# AIRZAI_LED_STRIP_FLEX_REVA_7p5Pitch.net
KiCad netlist of a schematic drawn in Altium Designer
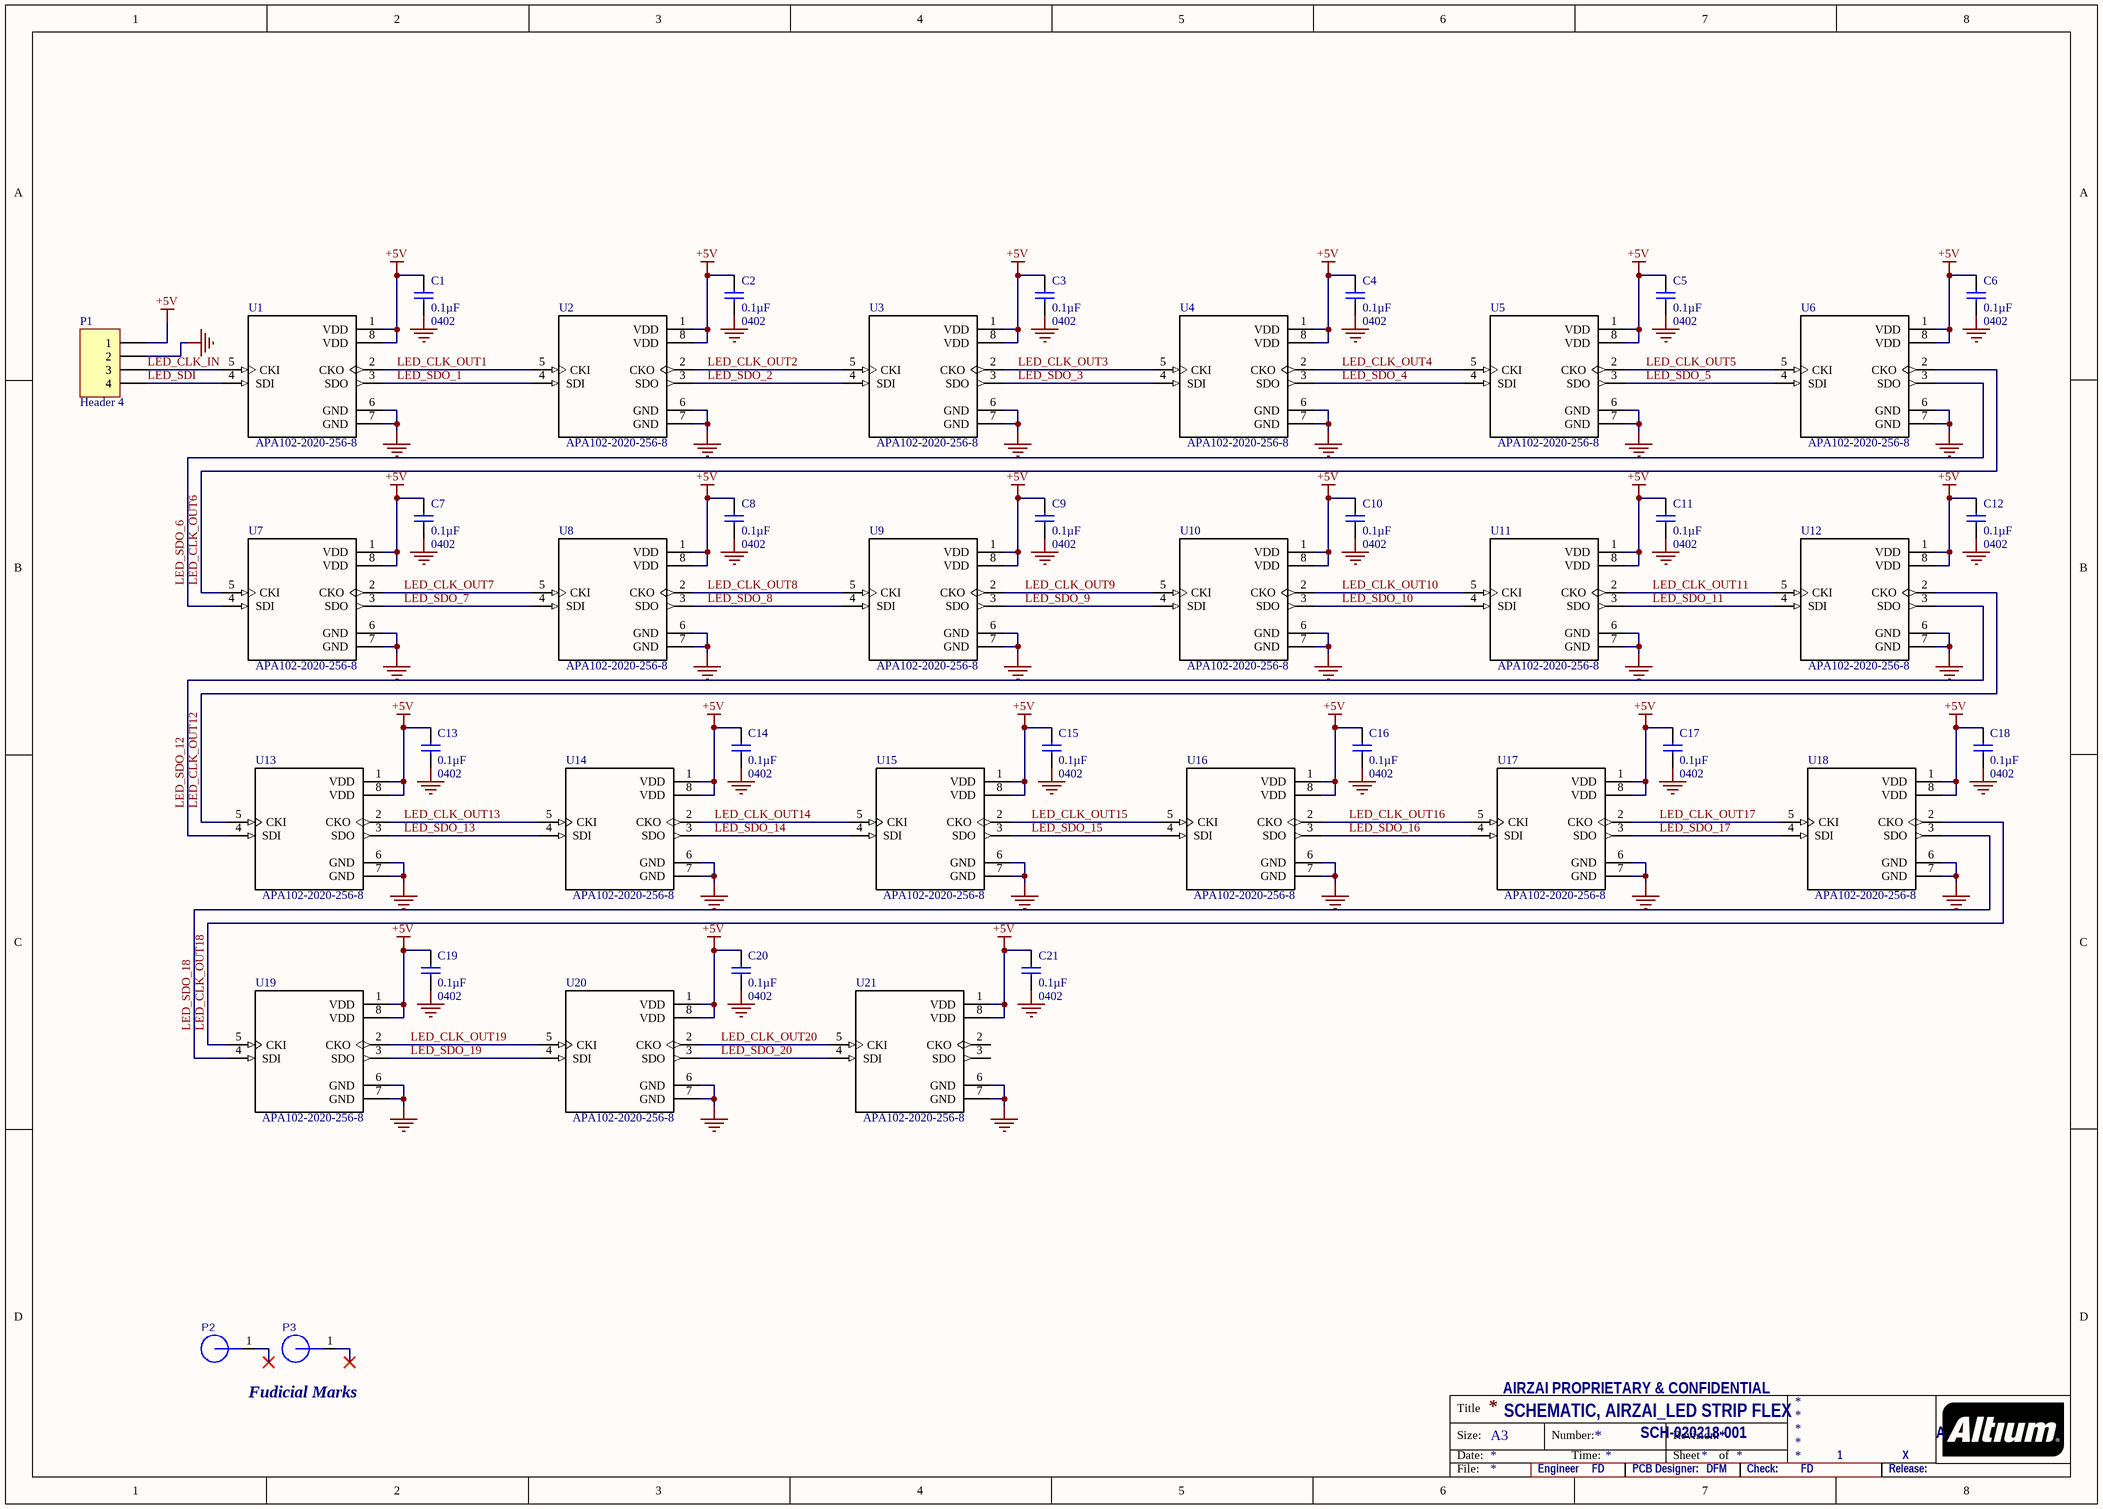
[diagram p0: AIRZAI_LED_STRIP_FLEX_REVA_7p5Pitch.SchDoc]

(export (version "E")
  (design (tool "Eeschema 10.0.6"))
  (components
    (comp (ref "C1")
      (value "0.1µF")
      (footprint "0402")
      (description "Capacitor, X7R, ±10%")
      (fields (field (name "MANUFACTURER") "TDK") (field (name "MANUFACTURER PART NUMBER") "C1005X7R1C104K"))
      (libsource (lib "Nordic Passive DB") (part "CAP"))
    )
    (comp (ref "C2")
      (value "0.1µF")
      (footprint "0402")
      (description "Capacitor, X7R, ±10%")
      (fields (field (name "MANUFACTURER") "TDK") (field (name "MANUFACTURER PART NUMBER") "C1005X7R1C104K"))
      (libsource (lib "Nordic Passive DB") (part "CAP"))
    )
    (comp (ref "C3")
      (value "0.1µF")
      (footprint "0402")
      (description "Capacitor, X7R, ±10%")
      (fields (field (name "MANUFACTURER") "TDK") (field (name "MANUFACTURER PART NUMBER") "C1005X7R1C104K"))
      (libsource (lib "Nordic Passive DB") (part "CAP"))
    )
    (comp (ref "C4")
      (value "0.1µF")
      (footprint "0402")
      (description "Capacitor, X7R, ±10%")
      (fields (field (name "MANUFACTURER") "TDK") (field (name "MANUFACTURER PART NUMBER") "C1005X7R1C104K"))
      (libsource (lib "Nordic Passive DB") (part "CAP"))
    )
    (comp (ref "C5")
      (value "0.1µF")
      (footprint "0402")
      (description "Capacitor, X7R, ±10%")
      (fields (field (name "MANUFACTURER") "TDK") (field (name "MANUFACTURER PART NUMBER") "C1005X7R1C104K"))
      (libsource (lib "Nordic Passive DB") (part "CAP"))
    )
    (comp (ref "C6")
      (value "0.1µF")
      (footprint "0402")
      (description "Capacitor, X7R, ±10%")
      (fields (field (name "MANUFACTURER") "TDK") (field (name "MANUFACTURER PART NUMBER") "C1005X7R1C104K"))
      (libsource (lib "Nordic Passive DB") (part "CAP"))
    )
    (comp (ref "C7")
      (value "0.1µF")
      (footprint "0402")
      (description "Capacitor, X7R, ±10%")
      (fields (field (name "MANUFACTURER") "TDK") (field (name "MANUFACTURER PART NUMBER") "C1005X7R1C104K"))
      (libsource (lib "Nordic Passive DB") (part "CAP"))
    )
    (comp (ref "C8")
      (value "0.1µF")
      (footprint "0402")
      (description "Capacitor, X7R, ±10%")
      (fields (field (name "MANUFACTURER") "TDK") (field (name "MANUFACTURER PART NUMBER") "C1005X7R1C104K"))
      (libsource (lib "Nordic Passive DB") (part "CAP"))
    )
    (comp (ref "C9")
      (value "0.1µF")
      (footprint "0402")
      (description "Capacitor, X7R, ±10%")
      (fields (field (name "MANUFACTURER") "TDK") (field (name "MANUFACTURER PART NUMBER") "C1005X7R1C104K"))
      (libsource (lib "Nordic Passive DB") (part "CAP"))
    )
    (comp (ref "C10")
      (value "0.1µF")
      (footprint "0402")
      (description "Capacitor, X7R, ±10%")
      (fields (field (name "MANUFACTURER") "TDK") (field (name "MANUFACTURER PART NUMBER") "C1005X7R1C104K"))
      (libsource (lib "Nordic Passive DB") (part "CAP"))
    )
    (comp (ref "C11")
      (value "0.1µF")
      (footprint "0402")
      (description "Capacitor, X7R, ±10%")
      (fields (field (name "MANUFACTURER") "TDK") (field (name "MANUFACTURER PART NUMBER") "C1005X7R1C104K"))
      (libsource (lib "Nordic Passive DB") (part "CAP"))
    )
    (comp (ref "C12")
      (value "0.1µF")
      (footprint "0402")
      (description "Capacitor, X7R, ±10%")
      (fields (field (name "MANUFACTURER") "TDK") (field (name "MANUFACTURER PART NUMBER") "C1005X7R1C104K"))
      (libsource (lib "Nordic Passive DB") (part "CAP"))
    )
    (comp (ref "C13")
      (value "0.1µF")
      (footprint "0402")
      (description "Capacitor, X7R, ±10%")
      (fields (field (name "MANUFACTURER") "TDK") (field (name "MANUFACTURER PART NUMBER") "C1005X7R1C104K"))
      (libsource (lib "Nordic Passive DB") (part "CAP"))
    )
    (comp (ref "C14")
      (value "0.1µF")
      (footprint "0402")
      (description "Capacitor, X7R, ±10%")
      (fields (field (name "MANUFACTURER") "TDK") (field (name "MANUFACTURER PART NUMBER") "C1005X7R1C104K"))
      (libsource (lib "Nordic Passive DB") (part "CAP"))
    )
    (comp (ref "C15")
      (value "0.1µF")
      (footprint "0402")
      (description "Capacitor, X7R, ±10%")
      (fields (field (name "MANUFACTURER") "TDK") (field (name "MANUFACTURER PART NUMBER") "C1005X7R1C104K"))
      (libsource (lib "Nordic Passive DB") (part "CAP"))
    )
    (comp (ref "C16")
      (value "0.1µF")
      (footprint "0402")
      (description "Capacitor, X7R, ±10%")
      (fields (field (name "MANUFACTURER") "TDK") (field (name "MANUFACTURER PART NUMBER") "C1005X7R1C104K"))
      (libsource (lib "Nordic Passive DB") (part "CAP"))
    )
    (comp (ref "C17")
      (value "0.1µF")
      (footprint "0402")
      (description "Capacitor, X7R, ±10%")
      (fields (field (name "MANUFACTURER") "TDK") (field (name "MANUFACTURER PART NUMBER") "C1005X7R1C104K"))
      (libsource (lib "Nordic Passive DB") (part "CAP"))
    )
    (comp (ref "C18")
      (value "0.1µF")
      (footprint "0402")
      (description "Capacitor, X7R, ±10%")
      (fields (field (name "MANUFACTURER") "TDK") (field (name "MANUFACTURER PART NUMBER") "C1005X7R1C104K"))
      (libsource (lib "Nordic Passive DB") (part "CAP"))
    )
    (comp (ref "C19")
      (value "0.1µF")
      (footprint "0402")
      (description "Capacitor, X7R, ±10%")
      (fields (field (name "MANUFACTURER") "TDK") (field (name "MANUFACTURER PART NUMBER") "C1005X7R1C104K"))
      (libsource (lib "Nordic Passive DB") (part "CAP"))
    )
    (comp (ref "C20")
      (value "0.1µF")
      (footprint "0402")
      (description "Capacitor, X7R, ±10%")
      (fields (field (name "MANUFACTURER") "TDK") (field (name "MANUFACTURER PART NUMBER") "C1005X7R1C104K"))
      (libsource (lib "Nordic Passive DB") (part "CAP"))
    )
    (comp (ref "C21")
      (value "0.1µF")
      (footprint "0402")
      (description "Capacitor, X7R, ±10%")
      (fields (field (name "MANUFACTURER") "TDK") (field (name "MANUFACTURER PART NUMBER") "C1005X7R1C104K"))
      (libsource (lib "Nordic Passive DB") (part "CAP"))
    )
    (comp (ref "P1")
      (value "Header 4")
      (footprint "FFC_4Pads")
      (description "Header, 4-Pin")
      (fields (field (name "PUBLISHER") "Altium Limited"))
      (libsource (lib "Miscellaneous Connectors") (part "Header 4"))
    )
    (comp (ref "P2") (value "~") (footprint "Fudicial") (libsource (lib "*") (part "TP")))
    (comp (ref "P3") (value "~") (footprint "Fudicial") (libsource (lib "*") (part "TP")))
    (comp (ref "U1")
      (value "APA102-2020-256-8")
      (footprint "APA102–2020")
      (description "DotStar Micro LEDs")
      (fields (field (name "MF") "Adafruit Industries") (field (name "MP") "APA-102-2020-256-8"))
      (libsource (lib "AIRZAI_LED_SENSE_FLEX_REVA") (part "APA102-2020-256-8"))
    )
    (comp (ref "U2")
      (value "APA102-2020-256-8")
      (footprint "APA102–2020")
      (description "DotStar Micro LEDs")
      (fields (field (name "MF") "Adafruit Industries") (field (name "MP") "APA-102-2020-256-8"))
      (libsource (lib "AIRZAI_LED_SENSE_FLEX_REVA") (part "APA102-2020-256-8"))
    )
    (comp (ref "U3")
      (value "APA102-2020-256-8")
      (footprint "APA102–2020")
      (description "DotStar Micro LEDs")
      (fields (field (name "MF") "Adafruit Industries") (field (name "MP") "APA-102-2020-256-8"))
      (libsource (lib "AIRZAI_LED_SENSE_FLEX_REVA") (part "APA102-2020-256-8"))
    )
    (comp (ref "U4")
      (value "APA102-2020-256-8")
      (footprint "APA102–2020")
      (description "DotStar Micro LEDs")
      (fields (field (name "MF") "Adafruit Industries") (field (name "MP") "APA-102-2020-256-8"))
      (libsource (lib "AIRZAI_LED_SENSE_FLEX_REVA") (part "APA102-2020-256-8"))
    )
    (comp (ref "U5")
      (value "APA102-2020-256-8")
      (footprint "APA102–2020")
      (description "DotStar Micro LEDs")
      (fields (field (name "MF") "Adafruit Industries") (field (name "MP") "APA-102-2020-256-8"))
      (libsource (lib "AIRZAI_LED_SENSE_FLEX_REVA") (part "APA102-2020-256-8"))
    )
    (comp (ref "U6")
      (value "APA102-2020-256-8")
      (footprint "APA102–2020")
      (description "DotStar Micro LEDs")
      (fields (field (name "MF") "Adafruit Industries") (field (name "MP") "APA-102-2020-256-8"))
      (libsource (lib "AIRZAI_LED_SENSE_FLEX_REVA") (part "APA102-2020-256-8"))
    )
    (comp (ref "U7")
      (value "APA102-2020-256-8")
      (footprint "APA102–2020")
      (description "DotStar Micro LEDs")
      (fields (field (name "MF") "Adafruit Industries") (field (name "MP") "APA-102-2020-256-8"))
      (libsource (lib "AIRZAI_LED_SENSE_FLEX_REVA") (part "APA102-2020-256-8"))
    )
    (comp (ref "U8")
      (value "APA102-2020-256-8")
      (footprint "APA102–2020")
      (description "DotStar Micro LEDs")
      (fields (field (name "MF") "Adafruit Industries") (field (name "MP") "APA-102-2020-256-8"))
      (libsource (lib "AIRZAI_LED_SENSE_FLEX_REVA") (part "APA102-2020-256-8"))
    )
    (comp (ref "U9")
      (value "APA102-2020-256-8")
      (footprint "APA102–2020")
      (description "DotStar Micro LEDs")
      (fields (field (name "MF") "Adafruit Industries") (field (name "MP") "APA-102-2020-256-8"))
      (libsource (lib "AIRZAI_LED_SENSE_FLEX_REVA") (part "APA102-2020-256-8"))
    )
    (comp (ref "U10")
      (value "APA102-2020-256-8")
      (footprint "APA102–2020")
      (description "DotStar Micro LEDs")
      (fields (field (name "MF") "Adafruit Industries") (field (name "MP") "APA-102-2020-256-8"))
      (libsource (lib "AIRZAI_LED_SENSE_FLEX_REVA") (part "APA102-2020-256-8"))
    )
    (comp (ref "U11")
      (value "APA102-2020-256-8")
      (footprint "APA102–2020")
      (description "DotStar Micro LEDs")
      (fields (field (name "MF") "Adafruit Industries") (field (name "MP") "APA-102-2020-256-8"))
      (libsource (lib "AIRZAI_LED_SENSE_FLEX_REVA") (part "APA102-2020-256-8"))
    )
    (comp (ref "U12")
      (value "APA102-2020-256-8")
      (footprint "APA102–2020")
      (description "DotStar Micro LEDs")
      (fields (field (name "MF") "Adafruit Industries") (field (name "MP") "APA-102-2020-256-8"))
      (libsource (lib "AIRZAI_LED_SENSE_FLEX_REVA") (part "APA102-2020-256-8"))
    )
    (comp (ref "U13")
      (value "APA102-2020-256-8")
      (footprint "APA102–2020")
      (description "DotStar Micro LEDs")
      (fields (field (name "MF") "Adafruit Industries") (field (name "MP") "APA-102-2020-256-8"))
      (libsource (lib "AIRZAI_LED_SENSE_FLEX_REVA") (part "APA102-2020-256-8"))
    )
    (comp (ref "U14")
      (value "APA102-2020-256-8")
      (footprint "APA102–2020")
      (description "DotStar Micro LEDs")
      (fields (field (name "MF") "Adafruit Industries") (field (name "MP") "APA-102-2020-256-8"))
      (libsource (lib "AIRZAI_LED_SENSE_FLEX_REVA") (part "APA102-2020-256-8"))
    )
    (comp (ref "U15")
      (value "APA102-2020-256-8")
      (footprint "APA102–2020")
      (description "DotStar Micro LEDs")
      (fields (field (name "MF") "Adafruit Industries") (field (name "MP") "APA-102-2020-256-8"))
      (libsource (lib "AIRZAI_LED_SENSE_FLEX_REVA") (part "APA102-2020-256-8"))
    )
    (comp (ref "U16")
      (value "APA102-2020-256-8")
      (footprint "APA102–2020")
      (description "DotStar Micro LEDs")
      (fields (field (name "MF") "Adafruit Industries") (field (name "MP") "APA-102-2020-256-8"))
      (libsource (lib "AIRZAI_LED_SENSE_FLEX_REVA") (part "APA102-2020-256-8"))
    )
    (comp (ref "U17")
      (value "APA102-2020-256-8")
      (footprint "APA102–2020")
      (description "DotStar Micro LEDs")
      (fields (field (name "MF") "Adafruit Industries") (field (name "MP") "APA-102-2020-256-8"))
      (libsource (lib "AIRZAI_LED_SENSE_FLEX_REVA") (part "APA102-2020-256-8"))
    )
    (comp (ref "U18")
      (value "APA102-2020-256-8")
      (footprint "APA102–2020")
      (description "DotStar Micro LEDs")
      (fields (field (name "MF") "Adafruit Industries") (field (name "MP") "APA-102-2020-256-8"))
      (libsource (lib "AIRZAI_LED_SENSE_FLEX_REVA") (part "APA102-2020-256-8"))
    )
    (comp (ref "U19")
      (value "APA102-2020-256-8")
      (footprint "APA102–2020")
      (description "DotStar Micro LEDs")
      (fields (field (name "MF") "Adafruit Industries") (field (name "MP") "APA-102-2020-256-8"))
      (libsource (lib "AIRZAI_LED_SENSE_FLEX_REVA") (part "APA102-2020-256-8"))
    )
    (comp (ref "U20")
      (value "APA102-2020-256-8")
      (footprint "APA102–2020")
      (description "DotStar Micro LEDs")
      (fields (field (name "MF") "Adafruit Industries") (field (name "MP") "APA-102-2020-256-8"))
      (libsource (lib "AIRZAI_LED_SENSE_FLEX_REVA") (part "APA102-2020-256-8"))
    )
    (comp (ref "U21")
      (value "APA102-2020-256-8")
      (footprint "APA102–2020")
      (description "DotStar Micro LEDs")
      (fields (field (name "MF") "Adafruit Industries") (field (name "MP") "APA-102-2020-256-8"))
      (libsource (lib "AIRZAI_LED_SENSE_FLEX_REVA") (part "APA102-2020-256-8"))
    )
  )
  (nets
    (net (code "1") (name "+5V") (class "Default")
      (node (ref "C1") (pin "1") (pinfunction "1_1") (pintype "passive"))
      (node (ref "C10") (pin "1") (pinfunction "1_1") (pintype "passive"))
      (node (ref "C11") (pin "1") (pinfunction "1_1") (pintype "passive"))
      (node (ref "C12") (pin "1") (pinfunction "1_1") (pintype "passive"))
      (node (ref "C13") (pin "1") (pinfunction "1_1") (pintype "passive"))
      (node (ref "C14") (pin "1") (pinfunction "1_1") (pintype "passive"))
      (node (ref "C15") (pin "1") (pinfunction "1_1") (pintype "passive"))
      (node (ref "C16") (pin "1") (pinfunction "1_1") (pintype "passive"))
      (node (ref "C17") (pin "1") (pinfunction "1_1") (pintype "passive"))
      (node (ref "C18") (pin "1") (pinfunction "1_1") (pintype "passive"))
      (node (ref "C19") (pin "1") (pinfunction "1_1") (pintype "passive"))
      (node (ref "C2") (pin "1") (pinfunction "1_1") (pintype "passive"))
      (node (ref "C20") (pin "1") (pinfunction "1_1") (pintype "passive"))
      (node (ref "C21") (pin "1") (pinfunction "1_1") (pintype "passive"))
      (node (ref "C3") (pin "1") (pinfunction "1_1") (pintype "passive"))
      (node (ref "C4") (pin "1") (pinfunction "1_1") (pintype "passive"))
      (node (ref "C5") (pin "1") (pinfunction "1_1") (pintype "passive"))
      (node (ref "C6") (pin "1") (pinfunction "1_1") (pintype "passive"))
      (node (ref "C7") (pin "1") (pinfunction "1_1") (pintype "passive"))
      (node (ref "C8") (pin "1") (pinfunction "1_1") (pintype "passive"))
      (node (ref "C9") (pin "1") (pinfunction "1_1") (pintype "passive"))
      (node (ref "P1") (pin "1") (pinfunction "1_1") (pintype "passive"))
      (node (ref "U1") (pin "1") (pinfunction "VDD_1") (pintype "power_in"))
      (node (ref "U1") (pin "8") (pinfunction "VDD_8") (pintype "power_in"))
      (node (ref "U10") (pin "1") (pinfunction "VDD_1") (pintype "power_in"))
      (node (ref "U10") (pin "8") (pinfunction "VDD_8") (pintype "power_in"))
      (node (ref "U11") (pin "1") (pinfunction "VDD_1") (pintype "power_in"))
      (node (ref "U11") (pin "8") (pinfunction "VDD_8") (pintype "power_in"))
      (node (ref "U12") (pin "1") (pinfunction "VDD_1") (pintype "power_in"))
      (node (ref "U12") (pin "8") (pinfunction "VDD_8") (pintype "power_in"))
      (node (ref "U13") (pin "1") (pinfunction "VDD_1") (pintype "power_in"))
      (node (ref "U13") (pin "8") (pinfunction "VDD_8") (pintype "power_in"))
      (node (ref "U14") (pin "1") (pinfunction "VDD_1") (pintype "power_in"))
      (node (ref "U14") (pin "8") (pinfunction "VDD_8") (pintype "power_in"))
      (node (ref "U15") (pin "1") (pinfunction "VDD_1") (pintype "power_in"))
      (node (ref "U15") (pin "8") (pinfunction "VDD_8") (pintype "power_in"))
      (node (ref "U16") (pin "1") (pinfunction "VDD_1") (pintype "power_in"))
      (node (ref "U16") (pin "8") (pinfunction "VDD_8") (pintype "power_in"))
      (node (ref "U17") (pin "1") (pinfunction "VDD_1") (pintype "power_in"))
      (node (ref "U17") (pin "8") (pinfunction "VDD_8") (pintype "power_in"))
      (node (ref "U18") (pin "1") (pinfunction "VDD_1") (pintype "power_in"))
      (node (ref "U18") (pin "8") (pinfunction "VDD_8") (pintype "power_in"))
      (node (ref "U19") (pin "1") (pinfunction "VDD_1") (pintype "power_in"))
      (node (ref "U19") (pin "8") (pinfunction "VDD_8") (pintype "power_in"))
      (node (ref "U2") (pin "1") (pinfunction "VDD_1") (pintype "power_in"))
      (node (ref "U2") (pin "8") (pinfunction "VDD_8") (pintype "power_in"))
      (node (ref "U20") (pin "1") (pinfunction "VDD_1") (pintype "power_in"))
      (node (ref "U20") (pin "8") (pinfunction "VDD_8") (pintype "power_in"))
      (node (ref "U21") (pin "1") (pinfunction "VDD_1") (pintype "power_in"))
      (node (ref "U21") (pin "8") (pinfunction "VDD_8") (pintype "power_in"))
      (node (ref "U3") (pin "1") (pinfunction "VDD_1") (pintype "power_in"))
      (node (ref "U3") (pin "8") (pinfunction "VDD_8") (pintype "power_in"))
      (node (ref "U4") (pin "1") (pinfunction "VDD_1") (pintype "power_in"))
      (node (ref "U4") (pin "8") (pinfunction "VDD_8") (pintype "power_in"))
      (node (ref "U5") (pin "1") (pinfunction "VDD_1") (pintype "power_in"))
      (node (ref "U5") (pin "8") (pinfunction "VDD_8") (pintype "power_in"))
      (node (ref "U6") (pin "1") (pinfunction "VDD_1") (pintype "power_in"))
      (node (ref "U6") (pin "8") (pinfunction "VDD_8") (pintype "power_in"))
      (node (ref "U7") (pin "1") (pinfunction "VDD_1") (pintype "power_in"))
      (node (ref "U7") (pin "8") (pinfunction "VDD_8") (pintype "power_in"))
      (node (ref "U8") (pin "1") (pinfunction "VDD_1") (pintype "power_in"))
      (node (ref "U8") (pin "8") (pinfunction "VDD_8") (pintype "power_in"))
      (node (ref "U9") (pin "1") (pinfunction "VDD_1") (pintype "power_in"))
      (node (ref "U9") (pin "8") (pinfunction "VDD_8") (pintype "power_in"))
    )
    (net (code "2") (name "/LED_CLK_IN") (class "Default")
      (node (ref "P1") (pin "3") (pinfunction "3_3") (pintype "passive"))
      (node (ref "U1") (pin "5") (pinfunction "CKI_5") (pintype "input"))
    )
    (net (code "3") (name "/LED_CLK_OUT1") (class "Default")
      (node (ref "U1") (pin "2") (pinfunction "CKO_2") (pintype "output"))
      (node (ref "U2") (pin "5") (pinfunction "CKI_5") (pintype "input"))
    )
    (net (code "4") (name "/LED_CLK_OUT2") (class "Default")
      (node (ref "U2") (pin "2") (pinfunction "CKO_2") (pintype "output"))
      (node (ref "U3") (pin "5") (pinfunction "CKI_5") (pintype "input"))
    )
    (net (code "5") (name "/LED_CLK_OUT3") (class "Default")
      (node (ref "U3") (pin "2") (pinfunction "CKO_2") (pintype "output"))
      (node (ref "U4") (pin "5") (pinfunction "CKI_5") (pintype "input"))
    )
    (net (code "6") (name "/LED_CLK_OUT4") (class "Default")
      (node (ref "U4") (pin "2") (pinfunction "CKO_2") (pintype "output"))
      (node (ref "U5") (pin "5") (pinfunction "CKI_5") (pintype "input"))
    )
    (net (code "7") (name "/LED_CLK_OUT5") (class "Default")
      (node (ref "U5") (pin "2") (pinfunction "CKO_2") (pintype "output"))
      (node (ref "U6") (pin "5") (pinfunction "CKI_5") (pintype "input"))
    )
    (net (code "8") (name "/LED_CLK_OUT6") (class "Default")
      (node (ref "U6") (pin "2") (pinfunction "CKO_2") (pintype "output"))
      (node (ref "U7") (pin "5") (pinfunction "CKI_5") (pintype "input"))
    )
    (net (code "9") (name "/LED_CLK_OUT7") (class "Default")
      (node (ref "U7") (pin "2") (pinfunction "CKO_2") (pintype "output"))
      (node (ref "U8") (pin "5") (pinfunction "CKI_5") (pintype "input"))
    )
    (net (code "10") (name "/LED_CLK_OUT8") (class "Default")
      (node (ref "U8") (pin "2") (pinfunction "CKO_2") (pintype "output"))
      (node (ref "U9") (pin "5") (pinfunction "CKI_5") (pintype "input"))
    )
    (net (code "11") (name "/LED_CLK_OUT9") (class "Default")
      (node (ref "U10") (pin "5") (pinfunction "CKI_5") (pintype "input"))
      (node (ref "U9") (pin "2") (pinfunction "CKO_2") (pintype "output"))
    )
    (net (code "12") (name "/LED_CLK_OUT10") (class "Default")
      (node (ref "U10") (pin "2") (pinfunction "CKO_2") (pintype "output"))
      (node (ref "U11") (pin "5") (pinfunction "CKI_5") (pintype "input"))
    )
    (net (code "13") (name "/LED_CLK_OUT11") (class "Default")
      (node (ref "U11") (pin "2") (pinfunction "CKO_2") (pintype "output"))
      (node (ref "U12") (pin "5") (pinfunction "CKI_5") (pintype "input"))
    )
    (net (code "14") (name "/LED_CLK_OUT12") (class "Default")
      (node (ref "U12") (pin "2") (pinfunction "CKO_2") (pintype "output"))
      (node (ref "U13") (pin "5") (pinfunction "CKI_5") (pintype "input"))
    )
    (net (code "15") (name "/LED_CLK_OUT13") (class "Default")
      (node (ref "U13") (pin "2") (pinfunction "CKO_2") (pintype "output"))
      (node (ref "U14") (pin "5") (pinfunction "CKI_5") (pintype "input"))
    )
    (net (code "16") (name "/LED_CLK_OUT14") (class "Default")
      (node (ref "U14") (pin "2") (pinfunction "CKO_2") (pintype "output"))
      (node (ref "U15") (pin "5") (pinfunction "CKI_5") (pintype "input"))
    )
    (net (code "17") (name "/LED_CLK_OUT15") (class "Default")
      (node (ref "U15") (pin "2") (pinfunction "CKO_2") (pintype "output"))
      (node (ref "U16") (pin "5") (pinfunction "CKI_5") (pintype "input"))
    )
    (net (code "18") (name "/LED_CLK_OUT16") (class "Default")
      (node (ref "U16") (pin "2") (pinfunction "CKO_2") (pintype "output"))
      (node (ref "U17") (pin "5") (pinfunction "CKI_5") (pintype "input"))
    )
    (net (code "19") (name "/LED_CLK_OUT17") (class "Default")
      (node (ref "U17") (pin "2") (pinfunction "CKO_2") (pintype "output"))
      (node (ref "U18") (pin "5") (pinfunction "CKI_5") (pintype "input"))
    )
    (net (code "20") (name "/LED_CLK_OUT18") (class "Default")
      (node (ref "U18") (pin "2") (pinfunction "CKO_2") (pintype "output"))
      (node (ref "U19") (pin "5") (pinfunction "CKI_5") (pintype "input"))
    )
    (net (code "21") (name "/LED_CLK_OUT19") (class "Default")
      (node (ref "U19") (pin "2") (pinfunction "CKO_2") (pintype "output"))
      (node (ref "U20") (pin "5") (pinfunction "CKI_5") (pintype "input"))
    )
    (net (code "22") (name "/LED_CLK_OUT20") (class "Default")
      (node (ref "U20") (pin "2") (pinfunction "CKO_2") (pintype "output"))
      (node (ref "U21") (pin "5") (pinfunction "CKI_5") (pintype "input"))
    )
    (net (code "23") (name "/LED_SDI") (class "Default")
      (node (ref "P1") (pin "4") (pinfunction "4_4") (pintype "passive"))
      (node (ref "U1") (pin "4") (pinfunction "SDI_4") (pintype "input"))
    )
    (net (code "24") (name "/LED_SDO_1") (class "Default")
      (node (ref "U1") (pin "3") (pinfunction "SDO_3") (pintype "output"))
      (node (ref "U2") (pin "4") (pinfunction "SDI_4") (pintype "input"))
    )
    (net (code "25") (name "/LED_SDO_2") (class "Default")
      (node (ref "U2") (pin "3") (pinfunction "SDO_3") (pintype "output"))
      (node (ref "U3") (pin "4") (pinfunction "SDI_4") (pintype "input"))
    )
    (net (code "26") (name "/LED_SDO_3") (class "Default")
      (node (ref "U3") (pin "3") (pinfunction "SDO_3") (pintype "output"))
      (node (ref "U4") (pin "4") (pinfunction "SDI_4") (pintype "input"))
    )
    (net (code "27") (name "/LED_SDO_4") (class "Default")
      (node (ref "U4") (pin "3") (pinfunction "SDO_3") (pintype "output"))
      (node (ref "U5") (pin "4") (pinfunction "SDI_4") (pintype "input"))
    )
    (net (code "28") (name "/LED_SDO_5") (class "Default")
      (node (ref "U5") (pin "3") (pinfunction "SDO_3") (pintype "output"))
      (node (ref "U6") (pin "4") (pinfunction "SDI_4") (pintype "input"))
    )
    (net (code "29") (name "/LED_SDO_6") (class "Default")
      (node (ref "U6") (pin "3") (pinfunction "SDO_3") (pintype "output"))
      (node (ref "U7") (pin "4") (pinfunction "SDI_4") (pintype "input"))
    )
    (net (code "30") (name "/LED_SDO_7") (class "Default")
      (node (ref "U7") (pin "3") (pinfunction "SDO_3") (pintype "output"))
      (node (ref "U8") (pin "4") (pinfunction "SDI_4") (pintype "input"))
    )
    (net (code "31") (name "/LED_SDO_8") (class "Default")
      (node (ref "U8") (pin "3") (pinfunction "SDO_3") (pintype "output"))
      (node (ref "U9") (pin "4") (pinfunction "SDI_4") (pintype "input"))
    )
    (net (code "32") (name "/LED_SDO_9") (class "Default")
      (node (ref "U10") (pin "4") (pinfunction "SDI_4") (pintype "input"))
      (node (ref "U9") (pin "3") (pinfunction "SDO_3") (pintype "output"))
    )
    (net (code "33") (name "/LED_SDO_10") (class "Default")
      (node (ref "U10") (pin "3") (pinfunction "SDO_3") (pintype "output"))
      (node (ref "U11") (pin "4") (pinfunction "SDI_4") (pintype "input"))
    )
    (net (code "34") (name "/LED_SDO_11") (class "Default")
      (node (ref "U11") (pin "3") (pinfunction "SDO_3") (pintype "output"))
      (node (ref "U12") (pin "4") (pinfunction "SDI_4") (pintype "input"))
    )
    (net (code "35") (name "/LED_SDO_12") (class "Default")
      (node (ref "U12") (pin "3") (pinfunction "SDO_3") (pintype "output"))
      (node (ref "U13") (pin "4") (pinfunction "SDI_4") (pintype "input"))
    )
    (net (code "36") (name "/LED_SDO_13") (class "Default")
      (node (ref "U13") (pin "3") (pinfunction "SDO_3") (pintype "output"))
      (node (ref "U14") (pin "4") (pinfunction "SDI_4") (pintype "input"))
    )
    (net (code "37") (name "/LED_SDO_14") (class "Default")
      (node (ref "U14") (pin "3") (pinfunction "SDO_3") (pintype "output"))
      (node (ref "U15") (pin "4") (pinfunction "SDI_4") (pintype "input"))
    )
    (net (code "38") (name "/LED_SDO_15") (class "Default")
      (node (ref "U15") (pin "3") (pinfunction "SDO_3") (pintype "output"))
      (node (ref "U16") (pin "4") (pinfunction "SDI_4") (pintype "input"))
    )
    (net (code "39") (name "/LED_SDO_16") (class "Default")
      (node (ref "U16") (pin "3") (pinfunction "SDO_3") (pintype "output"))
      (node (ref "U17") (pin "4") (pinfunction "SDI_4") (pintype "input"))
    )
    (net (code "40") (name "/LED_SDO_17") (class "Default")
      (node (ref "U17") (pin "3") (pinfunction "SDO_3") (pintype "output"))
      (node (ref "U18") (pin "4") (pinfunction "SDI_4") (pintype "input"))
    )
    (net (code "41") (name "/LED_SDO_18") (class "Default")
      (node (ref "U18") (pin "3") (pinfunction "SDO_3") (pintype "output"))
      (node (ref "U19") (pin "4") (pinfunction "SDI_4") (pintype "input"))
    )
    (net (code "42") (name "/LED_SDO_19") (class "Default")
      (node (ref "U19") (pin "3") (pinfunction "SDO_3") (pintype "output"))
      (node (ref "U20") (pin "4") (pinfunction "SDI_4") (pintype "input"))
    )
    (net (code "43") (name "/LED_SDO_20") (class "Default")
      (node (ref "U20") (pin "3") (pinfunction "SDO_3") (pintype "output"))
      (node (ref "U21") (pin "4") (pinfunction "SDI_4") (pintype "input"))
    )
    (net (code "44") (name "GND") (class "Default")
      (node (ref "C1") (pin "2") (pinfunction "2_2") (pintype "passive"))
      (node (ref "C10") (pin "2") (pinfunction "2_2") (pintype "passive"))
      (node (ref "C11") (pin "2") (pinfunction "2_2") (pintype "passive"))
      (node (ref "C12") (pin "2") (pinfunction "2_2") (pintype "passive"))
      (node (ref "C13") (pin "2") (pinfunction "2_2") (pintype "passive"))
      (node (ref "C14") (pin "2") (pinfunction "2_2") (pintype "passive"))
      (node (ref "C15") (pin "2") (pinfunction "2_2") (pintype "passive"))
      (node (ref "C16") (pin "2") (pinfunction "2_2") (pintype "passive"))
      (node (ref "C17") (pin "2") (pinfunction "2_2") (pintype "passive"))
      (node (ref "C18") (pin "2") (pinfunction "2_2") (pintype "passive"))
      (node (ref "C19") (pin "2") (pinfunction "2_2") (pintype "passive"))
      (node (ref "C2") (pin "2") (pinfunction "2_2") (pintype "passive"))
      (node (ref "C20") (pin "2") (pinfunction "2_2") (pintype "passive"))
      (node (ref "C21") (pin "2") (pinfunction "2_2") (pintype "passive"))
      (node (ref "C3") (pin "2") (pinfunction "2_2") (pintype "passive"))
      (node (ref "C4") (pin "2") (pinfunction "2_2") (pintype "passive"))
      (node (ref "C5") (pin "2") (pinfunction "2_2") (pintype "passive"))
      (node (ref "C6") (pin "2") (pinfunction "2_2") (pintype "passive"))
      (node (ref "C7") (pin "2") (pinfunction "2_2") (pintype "passive"))
      (node (ref "C8") (pin "2") (pinfunction "2_2") (pintype "passive"))
      (node (ref "C9") (pin "2") (pinfunction "2_2") (pintype "passive"))
      (node (ref "P1") (pin "2") (pinfunction "2_2") (pintype "passive"))
      (node (ref "U1") (pin "6") (pinfunction "GND_6") (pintype "power_in"))
      (node (ref "U1") (pin "7") (pinfunction "GND_7") (pintype "power_in"))
      (node (ref "U10") (pin "6") (pinfunction "GND_6") (pintype "power_in"))
      (node (ref "U10") (pin "7") (pinfunction "GND_7") (pintype "power_in"))
      (node (ref "U11") (pin "6") (pinfunction "GND_6") (pintype "power_in"))
      (node (ref "U11") (pin "7") (pinfunction "GND_7") (pintype "power_in"))
      (node (ref "U12") (pin "6") (pinfunction "GND_6") (pintype "power_in"))
      (node (ref "U12") (pin "7") (pinfunction "GND_7") (pintype "power_in"))
      (node (ref "U13") (pin "6") (pinfunction "GND_6") (pintype "power_in"))
      (node (ref "U13") (pin "7") (pinfunction "GND_7") (pintype "power_in"))
      (node (ref "U14") (pin "6") (pinfunction "GND_6") (pintype "power_in"))
      (node (ref "U14") (pin "7") (pinfunction "GND_7") (pintype "power_in"))
      (node (ref "U15") (pin "6") (pinfunction "GND_6") (pintype "power_in"))
      (node (ref "U15") (pin "7") (pinfunction "GND_7") (pintype "power_in"))
      (node (ref "U16") (pin "6") (pinfunction "GND_6") (pintype "power_in"))
      (node (ref "U16") (pin "7") (pinfunction "GND_7") (pintype "power_in"))
      (node (ref "U17") (pin "6") (pinfunction "GND_6") (pintype "power_in"))
      (node (ref "U17") (pin "7") (pinfunction "GND_7") (pintype "power_in"))
      (node (ref "U18") (pin "6") (pinfunction "GND_6") (pintype "power_in"))
      (node (ref "U18") (pin "7") (pinfunction "GND_7") (pintype "power_in"))
      (node (ref "U19") (pin "6") (pinfunction "GND_6") (pintype "power_in"))
      (node (ref "U19") (pin "7") (pinfunction "GND_7") (pintype "power_in"))
      (node (ref "U2") (pin "6") (pinfunction "GND_6") (pintype "power_in"))
      (node (ref "U2") (pin "7") (pinfunction "GND_7") (pintype "power_in"))
      (node (ref "U20") (pin "6") (pinfunction "GND_6") (pintype "power_in"))
      (node (ref "U20") (pin "7") (pinfunction "GND_7") (pintype "power_in"))
      (node (ref "U21") (pin "6") (pinfunction "GND_6") (pintype "power_in"))
      (node (ref "U21") (pin "7") (pinfunction "GND_7") (pintype "power_in"))
      (node (ref "U3") (pin "6") (pinfunction "GND_6") (pintype "power_in"))
      (node (ref "U3") (pin "7") (pinfunction "GND_7") (pintype "power_in"))
      (node (ref "U4") (pin "6") (pinfunction "GND_6") (pintype "power_in"))
      (node (ref "U4") (pin "7") (pinfunction "GND_7") (pintype "power_in"))
      (node (ref "U5") (pin "6") (pinfunction "GND_6") (pintype "power_in"))
      (node (ref "U5") (pin "7") (pinfunction "GND_7") (pintype "power_in"))
      (node (ref "U6") (pin "6") (pinfunction "GND_6") (pintype "power_in"))
      (node (ref "U6") (pin "7") (pinfunction "GND_7") (pintype "power_in"))
      (node (ref "U7") (pin "6") (pinfunction "GND_6") (pintype "power_in"))
      (node (ref "U7") (pin "7") (pinfunction "GND_7") (pintype "power_in"))
      (node (ref "U8") (pin "6") (pinfunction "GND_6") (pintype "power_in"))
      (node (ref "U8") (pin "7") (pinfunction "GND_7") (pintype "power_in"))
      (node (ref "U9") (pin "6") (pinfunction "GND_6") (pintype "power_in"))
      (node (ref "U9") (pin "7") (pinfunction "GND_7") (pintype "power_in"))
    )
    (net (code "45") (name "unconnected-(P2-Pad1)") (class "Default")
      (node (ref "P2") (pin "1") (pinfunction "1_1") (pintype "passive+no_connect"))
    )
    (net (code "46") (name "unconnected-(P3-Pad1)") (class "Default")
      (node (ref "P3") (pin "1") (pinfunction "1_1") (pintype "passive+no_connect"))
    )
    (net (code "47") (name "unconnected-(U21-CKO-Pad2)") (class "Default")
      (node (ref "U21") (pin "2") (pinfunction "CKO_2") (pintype "output"))
    )
    (net (code "48") (name "unconnected-(U21-SDO-Pad3)") (class "Default")
      (node (ref "U21") (pin "3") (pinfunction "SDO_3") (pintype "output"))
    )
  )
)
